# SCH_lipo_for_purrcat_2023-10-06.net
KiCad netlist of a schematic drawn in EasyEDA
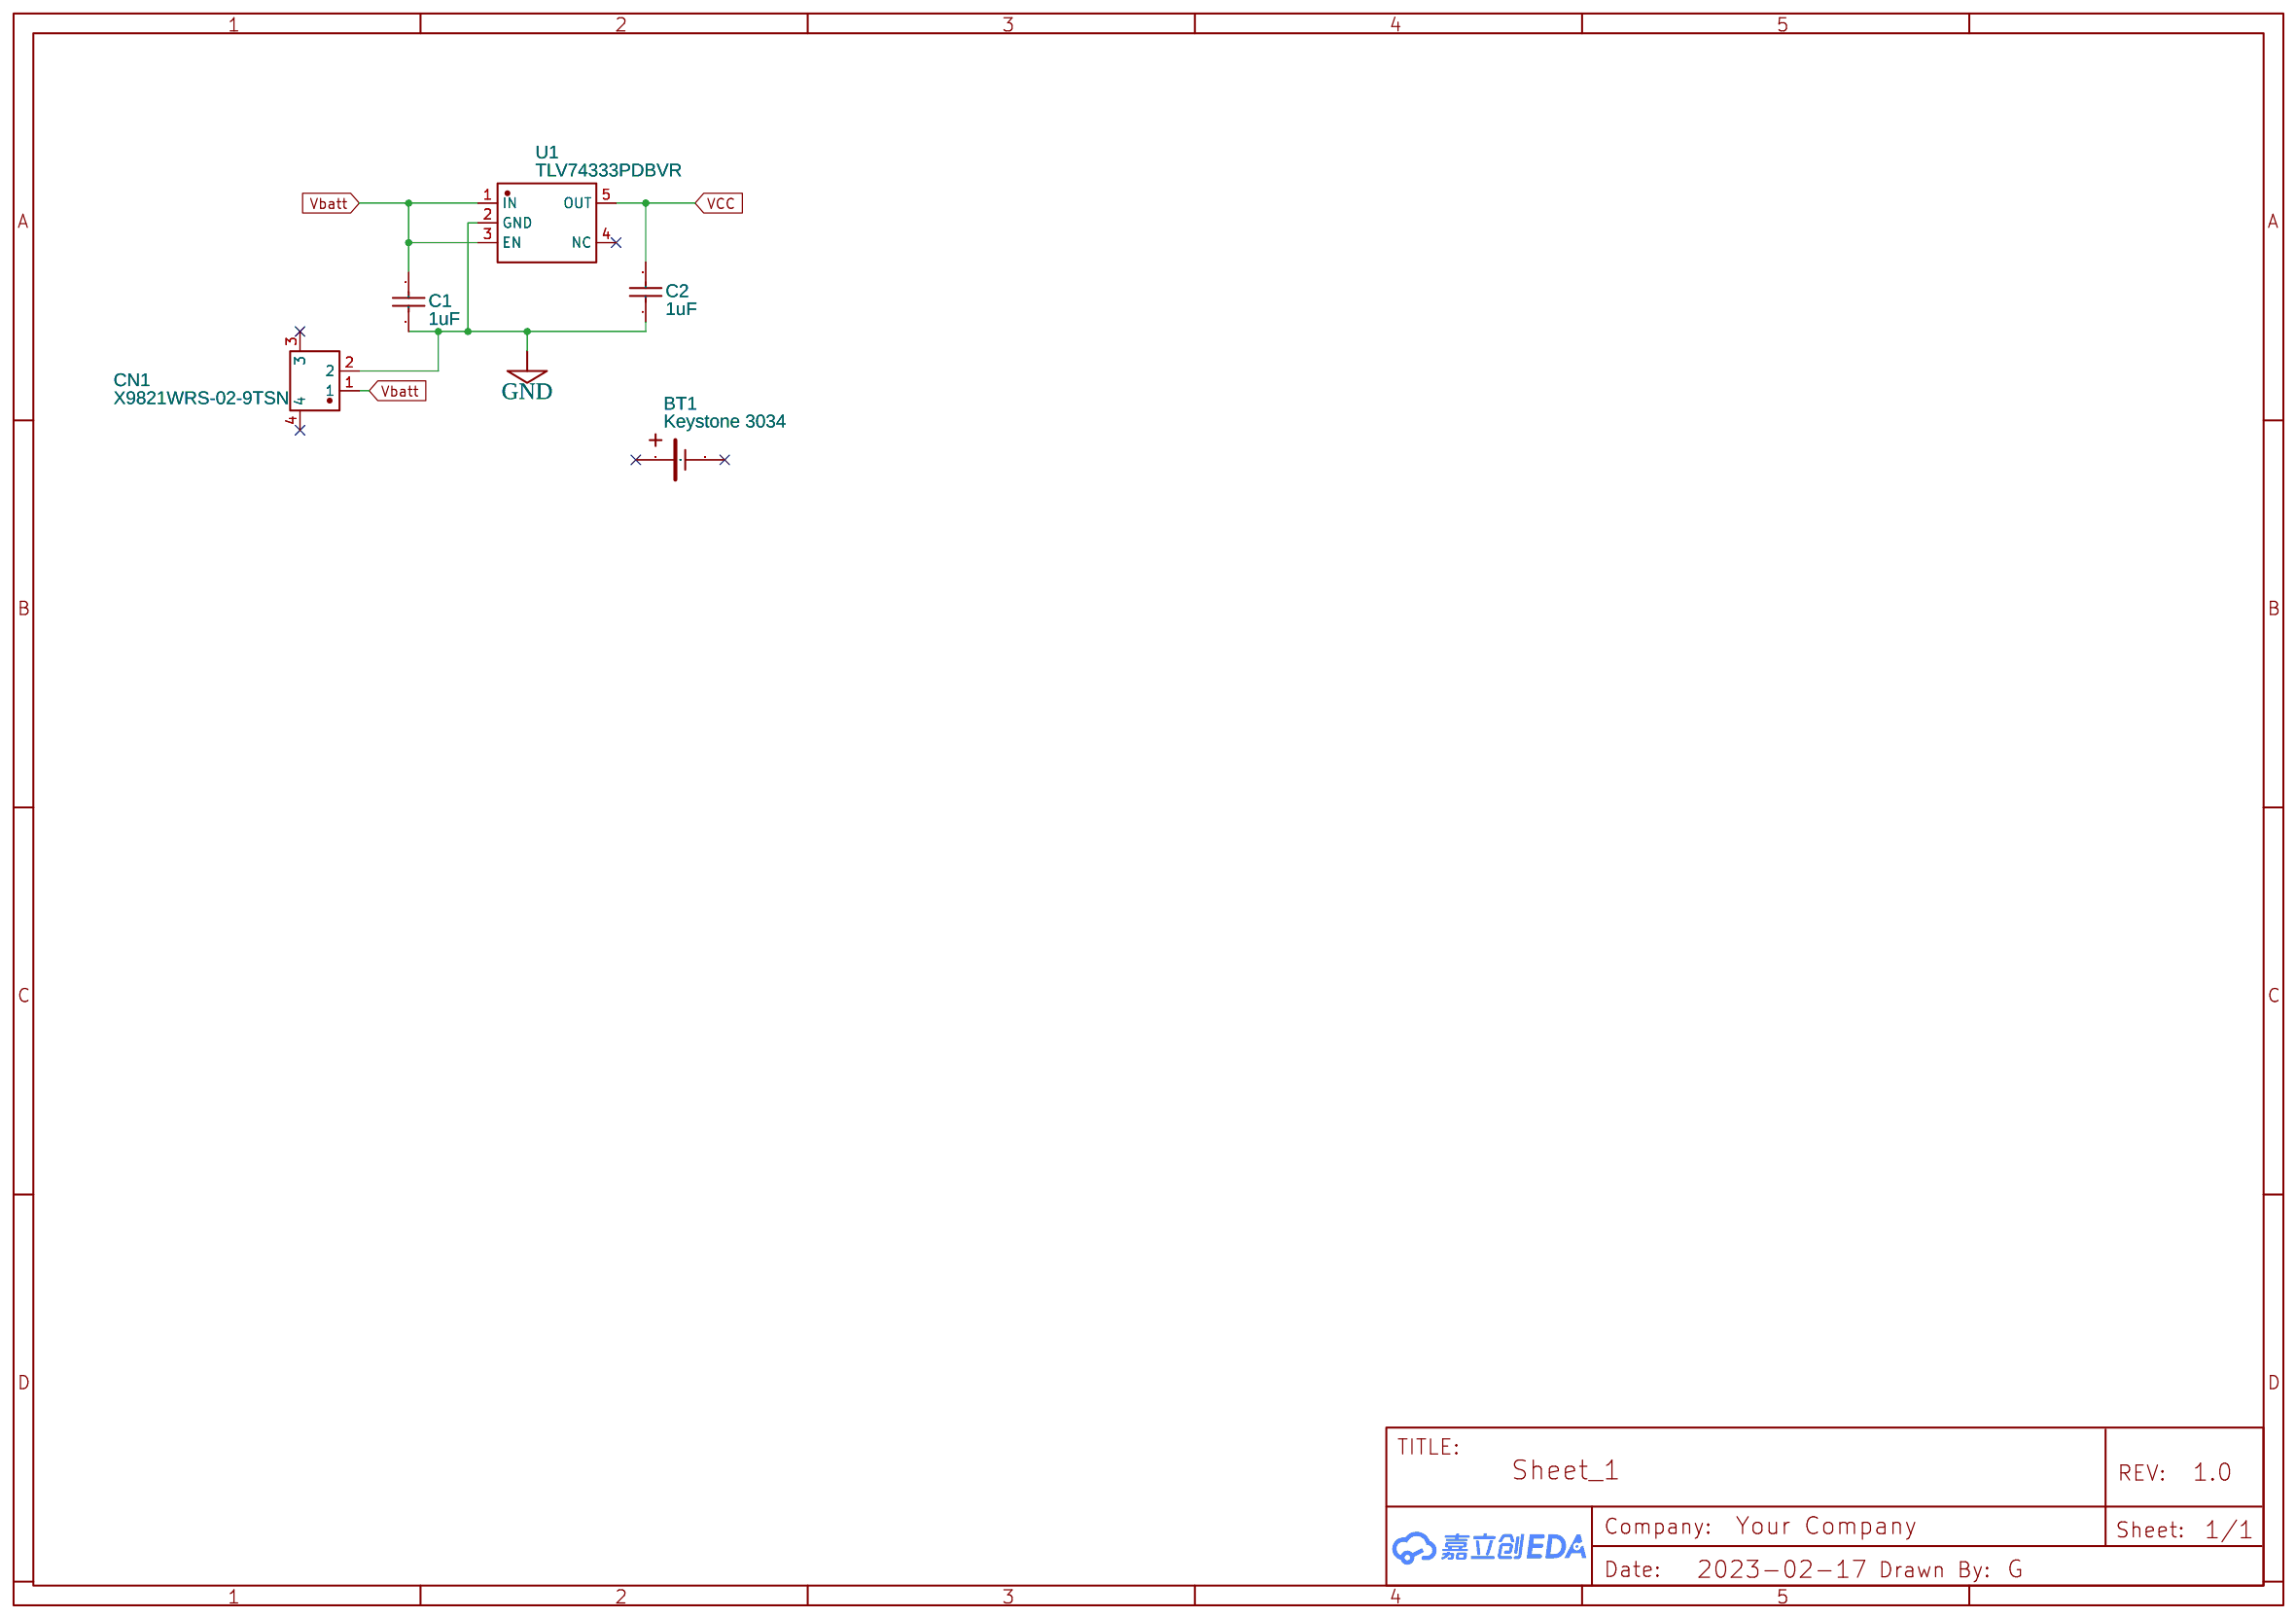
[diagram p0: schematic sheet]

(export (version "E")
  (design (tool "Eeschema 10.0.6"))
  (components
    (comp (ref "BT1")
      (value "Keystone 3034")
      (fields (field (name "Manufacturer Part") "3034") (field (name "Manufacturer") "Keystone Electronics"))
      (libsource (lib "") (part "Keystone 3034"))
    )
    (comp (ref "C1")
      (value "1uF")
      (fields
        (field (name "Manufacturer Part") "CL10B105KO8NNNC")
        (field (name "Manufacturer") "SAMSUNG(三星)")
      )
      (libsource (lib "") (part "CL10B105KO8NNNC"))
    )
    (comp (ref "C2")
      (value "1uF")
      (fields
        (field (name "Manufacturer Part") "CL10B105KO8NNNC")
        (field (name "Manufacturer") "SAMSUNG(三星)")
      )
      (libsource (lib "") (part "CL10B105KO8NNNC"))
    )
    (comp (ref "CN1")
      (value "X9821WRS-02-9TSN")
      (fields (field (name "Manufacturer") "XKB Connectivity(中国星坤)"))
      (libsource (lib "") (part "X9821WRS-02-9TSN"))
    )
    (comp (ref "U1")
      (value "TLV74333PDBVR")
      (fields (field (name "Manufacturer") "TI(德州仪器)"))
      (libsource (lib "") (part "TLV74333PDBVR"))
    )
  )
  (nets
    (net (code "1") (name "GND") (class "Default")
      (node (ref "C1") (pin "2") (pinfunction "2_2") (pintype "input"))
      (node (ref "C2") (pin "2") (pinfunction "2_2") (pintype "input"))
      (node (ref "CN1") (pin "2") (pinfunction "2_2") (pintype "unspecified"))
      (node (ref "U1") (pin "2") (pinfunction "GND_2") (pintype "unspecified"))
    )
    (net (code "2") (name "VCC") (class "Default")
      (node (ref "C2") (pin "1") (pinfunction "1_1") (pintype "input"))
      (node (ref "U1") (pin "5") (pinfunction "OUT_5") (pintype "unspecified"))
    )
    (net (code "3") (name "Vbatt") (class "Default")
      (node (ref "C1") (pin "1") (pinfunction "1_1") (pintype "input"))
      (node (ref "CN1") (pin "1") (pinfunction "1_1") (pintype "unspecified"))
      (node (ref "U1") (pin "1") (pinfunction "IN_1") (pintype "unspecified"))
      (node (ref "U1") (pin "3") (pinfunction "EN_3") (pintype "unspecified"))
    )
    (net (code "4") (name "unconnected-(BT1-Pad1)") (class "Default")
      (node (ref "BT1") (pin "1") (pinfunction "1_1") (pintype "unspecified+no_connect"))
    )
    (net (code "5") (name "unconnected-(BT1-Pad2)") (class "Default")
      (node (ref "BT1") (pin "2") (pinfunction "2_2") (pintype "unspecified+no_connect"))
    )
    (net (code "6") (name "unconnected-(CN1-Pad3)") (class "Default")
      (node (ref "CN1") (pin "3") (pinfunction "3_3") (pintype "unspecified+no_connect"))
    )
    (net (code "7") (name "unconnected-(CN1-Pad4)") (class "Default")
      (node (ref "CN1") (pin "4") (pinfunction "4_4") (pintype "unspecified+no_connect"))
    )
    (net (code "8") (name "unconnected-(U1-NC-Pad4)") (class "Default")
      (node (ref "U1") (pin "4") (pinfunction "NC_4") (pintype "unspecified+no_connect"))
    )
  )
)
